# Boom_Control_Board.net
KiCad netlist of a schematic drawn in EAGLE
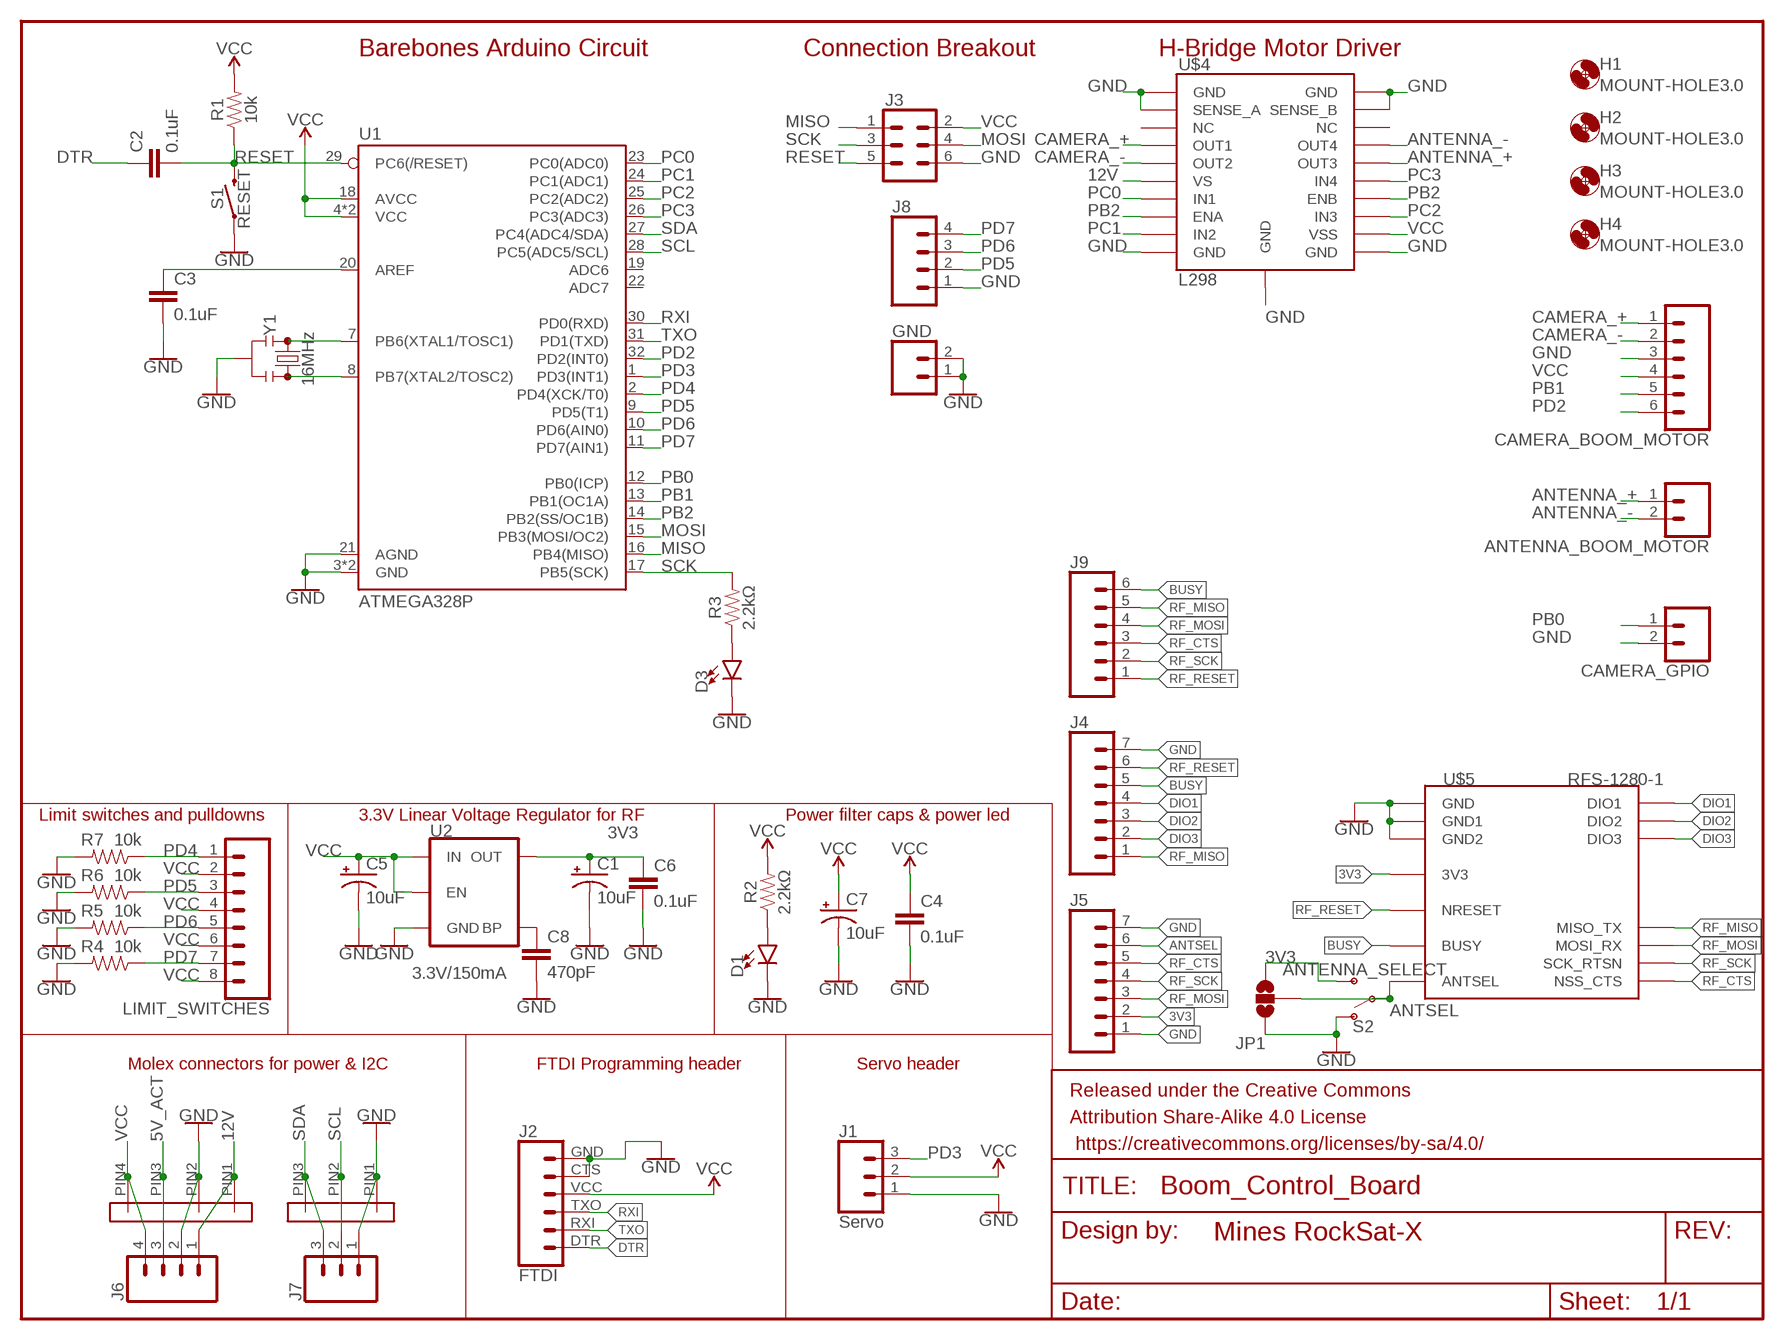
[diagram p0: schematic, sheet 1]

(export (version "E")
  (design (tool "Eeschema 10.0.6"))
  (components
    (comp (ref "ANTENNA_BOOM_MOTOR")
      (value "CONN_02LOCK_LONGPADS")
      (footprint "eagle-import:1X02_LOCK_LONGPADS")
      (libsource (lib "eagle-import") (part "CONN_02LOCK_LONGPADS"))
    )
    (comp (ref "C1")
      (value "10uF")
      (footprint "eagle-import:EIA3216")
      (libsource (lib "eagle-import") (part "10UF-POLAR-EIA3216-16V-10%(TANT)"))
    )
    (comp (ref "C2")
      (value "0.1uF")
      (footprint "eagle-import:0805")
      (libsource (lib "eagle-import") (part "2.2UF-0805-25V-(+80/-20%)"))
    )
    (comp (ref "C3")
      (value "0.1uF")
      (footprint "eagle-import:0805")
      (libsource (lib "eagle-import") (part "2.2UF-0805-25V-(+80/-20%)"))
    )
    (comp (ref "C4")
      (value "0.1uF")
      (footprint "eagle-import:0805")
      (libsource (lib "eagle-import") (part "2.2UF-0805-25V-(+80/-20%)"))
    )
    (comp (ref "C5")
      (value "10uF")
      (footprint "eagle-import:EIA3216")
      (libsource (lib "eagle-import") (part "10UF-POLAR-EIA3216-16V-10%(TANT)"))
    )
    (comp (ref "C6")
      (value "0.1uF")
      (footprint "eagle-import:0805")
      (libsource (lib "eagle-import") (part "2.2UF-0805-25V-(+80/-20%)"))
    )
    (comp (ref "C7")
      (value "10uF")
      (footprint "eagle-import:EIA3216")
      (libsource (lib "eagle-import") (part "10UF-POLAR-EIA3216-16V-10%(TANT)"))
    )
    (comp (ref "C8")
      (value "470pF")
      (footprint "eagle-import:0805")
      (libsource (lib "eagle-import") (part "CAP-0805"))
    )
    (comp (ref "CAMERA_BOOM_MOTOR")
      (value "CONN_06LOCK_LONGPADS")
      (footprint "eagle-import:1X06_LOCK_LONGPADS")
      (libsource (lib "eagle-import") (part "CONN_06LOCK_LONGPADS"))
    )
    (comp (ref "CAMERA_GPIO")
      (value "CONN_02LOCK_LONGPADS")
      (footprint "eagle-import:1X02_LOCK_LONGPADS")
      (libsource (lib "eagle-import") (part "CONN_02LOCK_LONGPADS"))
    )
    (comp (ref "D1")
      (value "LED-GREEN1206")
      (footprint "eagle-import:LED-1206")
      (libsource (lib "eagle-import") (part "LED-GREEN1206"))
    )
    (comp (ref "D3")
      (value "LED-GREEN1206")
      (footprint "eagle-import:LED-1206")
      (libsource (lib "eagle-import") (part "LED-GREEN1206"))
    )
    (comp (ref "FRAME1")
      (value "FRAME-LETTERNO_PACKAGE")
      (footprint "eagle-import:DUMMY")
      (fields
        (field (name "DESIGNER") "Mines RockSat-X")
        (field (name "VERSION") "1")
        (field (name "DESIGNER_1") "Mines RockSat-X")
      )
      (libsource (lib "eagle-import") (part "FRAME-LETTERNO_PACKAGE"))
    )
    (comp (ref "GND")
      (value "CONN_02LOCK_LONGPADS")
      (footprint "eagle-import:1X02_LOCK_LONGPADS")
      (libsource (lib "eagle-import") (part "CONN_02LOCK_LONGPADS"))
    )
    (comp (ref "H1")
      (value "MOUNT-HOLE3.0")
      (footprint "eagle-import:3,0")
      (libsource (lib "eagle-import") (part "MOUNT-HOLE3.0"))
    )
    (comp (ref "H2")
      (value "MOUNT-HOLE3.0")
      (footprint "eagle-import:3,0")
      (libsource (lib "eagle-import") (part "MOUNT-HOLE3.0"))
    )
    (comp (ref "H3")
      (value "MOUNT-HOLE3.0")
      (footprint "eagle-import:3,0")
      (libsource (lib "eagle-import") (part "MOUNT-HOLE3.0"))
    )
    (comp (ref "H4")
      (value "MOUNT-HOLE3.0")
      (footprint "eagle-import:3,0")
      (libsource (lib "eagle-import") (part "MOUNT-HOLE3.0"))
    )
    (comp (ref "J1")
      (value "Servo")
      (footprint "eagle-import:1X03")
      (libsource (lib "eagle-import") (part "CONN_03"))
    )
    (comp (ref "J2")
      (value "FTDI")
      (footprint "eagle-import:FTDI_BASIC")
      (libsource (lib "eagle-import") (part "6_PIN_SERIAL_CABLEPTH"))
    )
    (comp (ref "J3")
      (value "CONN_03X22X3_SILK_MALE_PTH")
      (footprint "eagle-import:2X3")
      (libsource (lib "eagle-import") (part "CONN_03X22X3_SILK_MALE_PTH"))
    )
    (comp (ref "J4")
      (value "CONN_07LOCK")
      (footprint "eagle-import:1X07_LOCK")
      (libsource (lib "eagle-import") (part "CONN_07LOCK"))
    )
    (comp (ref "J5")
      (value "CONN_07LOCK")
      (footprint "eagle-import:1X07_LOCK")
      (libsource (lib "eagle-import") (part "CONN_07LOCK"))
    )
    (comp (ref "J6")
      (value "CONN_04LOCK")
      (footprint "eagle-import:1X04_LOCK")
      (libsource (lib "eagle-import") (part "CONN_04LOCK"))
    )
    (comp (ref "J7")
      (value "CONN_03")
      (footprint "eagle-import:1X03")
      (libsource (lib "eagle-import") (part "CONN_03"))
    )
    (comp (ref "J8")
      (value "CONN_04LOCK")
      (footprint "eagle-import:1X04_LOCK")
      (libsource (lib "eagle-import") (part "CONN_04LOCK"))
    )
    (comp (ref "J9")
      (value "CONN_06LOCK")
      (footprint "eagle-import:1X06_LOCK")
      (libsource (lib "eagle-import") (part "CONN_06LOCK"))
    )
    (comp (ref "JP1")
      (value "JUMPER-SMT_3_NO_NO_SILK")
      (footprint "eagle-import:SMT-JUMPER_3_0-NO_TRACE_NO-SILK")
      (libsource (lib "eagle-import") (part "JUMPER-SMT_3_NO_NO_SILK"))
    )
    (comp (ref "LIMIT_SWITCHES")
      (value "CONN_08LOCK_LONGPADS")
      (footprint "eagle-import:1X08_LOCK_LONGPADS")
      (libsource (lib "eagle-import") (part "CONN_08LOCK_LONGPADS"))
    )
    (comp (ref "R1")
      (value "10k")
      (footprint "eagle-import:0805")
      (libsource (lib "eagle-import") (part "RESISTOR0805"))
    )
    (comp (ref "R2")
      (value "2.2kΩ")
      (footprint "eagle-import:0805")
      (libsource (lib "eagle-import") (part "RESISTOR0805"))
    )
    (comp (ref "R3")
      (value "2.2kΩ")
      (footprint "eagle-import:0805")
      (libsource (lib "eagle-import") (part "RESISTOR0805"))
    )
    (comp (ref "R4")
      (value "10k")
      (footprint "eagle-import:0805")
      (libsource (lib "eagle-import") (part "RESISTOR0805"))
    )
    (comp (ref "R5")
      (value "10k")
      (footprint "eagle-import:0805")
      (libsource (lib "eagle-import") (part "RESISTOR0805"))
    )
    (comp (ref "R6")
      (value "10k")
      (footprint "eagle-import:0805")
      (libsource (lib "eagle-import") (part "RESISTOR0805"))
    )
    (comp (ref "R7")
      (value "10k")
      (footprint "eagle-import:0805")
      (libsource (lib "eagle-import") (part "RESISTOR0805"))
    )
    (comp (ref "S1")
      (value "RESET")
      (footprint "eagle-import:TACTILE_SWITCH_SMD_5.2MM")
      (libsource (lib "eagle-import") (part "MOMENTARY-SWITCH-SPST-SMD-5.2-REDUNDANT"))
    )
    (comp (ref "S2")
      (value "ANTENNA_SELECT")
      (footprint "eagle-import:SWITCH_SPDT_PTH_11.6X4.0MM")
      (libsource (lib "eagle-import") (part "SWITCH-SPDT-PTH-11.6X4.0MM"))
    )
    (comp (ref "U$1")
      (value "MOLEX_4PIN")
      (footprint "eagle-import:MOLEX_4PIN")
      (libsource (lib "eagle-import") (part "MOLEX_4PIN"))
    )
    (comp (ref "U$2")
      (value "MOLEX_3PIN")
      (footprint "eagle-import:MOLEX_3PIN")
      (libsource (lib "eagle-import") (part "MOLEX_3PIN"))
    )
    (comp (ref "U$4")
      (value "L298")
      (footprint "eagle-import:POWERSO20_L298_PAD")
      (libsource (lib "eagle-import") (part "L298_SMD_W_PAD"))
    )
    (comp (ref "U$5")
      (value "RFS-1280-1")
      (footprint "eagle-import:RFS-1280-1")
      (libsource (lib "eagle-import") (part "RFS-1280-1"))
    )
    (comp (ref "U1")
      (value "ATMEGA328P")
      (footprint "eagle-import:TQFP32-08")
      (libsource (lib "eagle-import") (part "ATMEGA328P_TQFP"))
    )
    (comp (ref "U2")
      (value "3.3V/150mA")
      (footprint "eagle-import:SOT23-5")
      (libsource (lib "eagle-import") (part "V_REG_MIC52053.3V"))
    )
    (comp (ref "Y1")
      (value "16MHz")
      (footprint "eagle-import:RESONATOR-SMD-3.2X1.3")
      (libsource (lib "eagle-import") (part "RESONATOR-16MHZSMD_3.2X1.3"))
    )
  )
  (nets
    (net (code "1") (name "/5V_ACT") (class "Default")
      (node (ref "J6") (pin "3") (pinfunction "3_3") (pintype "passive"))
      (node (ref "U$1") (pin "PIN3") (pinfunction "PIN3_PIN3") (pintype "bidirectional"))
    )
    (net (code "2") (name "/12V") (class "Default")
      (node (ref "J6") (pin "1") (pinfunction "1_1") (pintype "passive"))
      (node (ref "U$1") (pin "PIN1") (pinfunction "PIN1_PIN1") (pintype "bidirectional"))
      (node (ref "U$4") (pin "6") (pinfunction "VS_6") (pintype "bidirectional"))
    )
    (net (code "3") (name "/ANTENNA_+") (class "Default")
      (node (ref "ANTENNA_BOOM_MOTOR") (pin "1") (pinfunction "1_1") (pintype "passive"))
      (node (ref "U$4") (pin "16") (pinfunction "OUT3_16") (pintype "bidirectional"))
    )
    (net (code "4") (name "/ANTENNA_-") (class "Default")
      (node (ref "ANTENNA_BOOM_MOTOR") (pin "2") (pinfunction "2_2") (pintype "passive"))
      (node (ref "U$4") (pin "17") (pinfunction "OUT4_17") (pintype "bidirectional"))
    )
    (net (code "5") (name "/CAMERA_+") (class "Default")
      (node (ref "CAMERA_BOOM_MOTOR") (pin "1") (pinfunction "1_1") (pintype "passive"))
      (node (ref "U$4") (pin "4") (pinfunction "OUT1_4") (pintype "bidirectional"))
    )
    (net (code "6") (name "/CAMERA_-") (class "Default")
      (node (ref "CAMERA_BOOM_MOTOR") (pin "2") (pinfunction "2_2") (pintype "passive"))
      (node (ref "U$4") (pin "5") (pinfunction "OUT2_5") (pintype "bidirectional"))
    )
    (net (code "7") (name "/MISO") (class "Default")
      (node (ref "J3") (pin "1") (pinfunction "1_1") (pintype "bidirectional"))
      (node (ref "U1") (pin "16") (pinfunction "PB4(MISO)_16") (pintype "bidirectional"))
    )
    (net (code "8") (name "/MOSI") (class "Default")
      (node (ref "J3") (pin "4") (pinfunction "4_4") (pintype "bidirectional"))
      (node (ref "U1") (pin "15") (pinfunction "PB3(MOSI/OC2)_15") (pintype "bidirectional"))
    )
    (net (code "9") (name "/PB0") (class "Default")
      (node (ref "CAMERA_GPIO") (pin "1") (pinfunction "1_1") (pintype "passive"))
      (node (ref "U1") (pin "12") (pinfunction "PB0(ICP)_12") (pintype "bidirectional"))
    )
    (net (code "10") (name "/PB1") (class "Default")
      (node (ref "CAMERA_BOOM_MOTOR") (pin "5") (pinfunction "5_5") (pintype "passive"))
      (node (ref "U1") (pin "13") (pinfunction "PB1(OC1A)_13") (pintype "bidirectional"))
    )
    (net (code "11") (name "/PB2") (class "Default")
      (node (ref "U$4") (pin "14") (pinfunction "ENB_14") (pintype "bidirectional"))
      (node (ref "U$4") (pin "8") (pinfunction "ENA_8") (pintype "bidirectional"))
      (node (ref "U1") (pin "14") (pinfunction "PB2(SS/OC1B)_14") (pintype "bidirectional"))
    )
    (net (code "12") (name "/PC0") (class "Default")
      (node (ref "U$4") (pin "7") (pinfunction "IN1_7") (pintype "bidirectional"))
      (node (ref "U1") (pin "23") (pinfunction "PC0(ADC0)_23") (pintype "bidirectional"))
    )
    (net (code "13") (name "/PC1") (class "Default")
      (node (ref "U$4") (pin "9") (pinfunction "IN2_9") (pintype "bidirectional"))
      (node (ref "U1") (pin "24") (pinfunction "PC1(ADC1)_24") (pintype "bidirectional"))
    )
    (net (code "14") (name "/PC2") (class "Default")
      (node (ref "U$4") (pin "13") (pinfunction "IN3_13") (pintype "bidirectional"))
      (node (ref "U1") (pin "25") (pinfunction "PC2(ADC2)_25") (pintype "bidirectional"))
    )
    (net (code "15") (name "/PC3") (class "Default")
      (node (ref "U$4") (pin "15") (pinfunction "IN4_15") (pintype "bidirectional"))
      (node (ref "U1") (pin "26") (pinfunction "PC3(ADC3)_26") (pintype "bidirectional"))
    )
    (net (code "16") (name "/PD2") (class "Default")
      (node (ref "CAMERA_BOOM_MOTOR") (pin "6") (pinfunction "6_6") (pintype "passive"))
      (node (ref "U1") (pin "32") (pinfunction "PD2(INT0)_32") (pintype "bidirectional"))
    )
    (net (code "17") (name "/PD3") (class "Default")
      (node (ref "J1") (pin "3") (pinfunction "3_3") (pintype "passive"))
      (node (ref "U1") (pin "1") (pinfunction "PD3(INT1)_1") (pintype "bidirectional"))
    )
    (net (code "18") (name "/PD4") (class "Default")
      (node (ref "LIMIT_SWITCHES") (pin "1") (pinfunction "1_1") (pintype "passive"))
      (node (ref "R7") (pin "1") (pinfunction "1_1") (pintype "passive"))
      (node (ref "U1") (pin "2") (pinfunction "PD4(XCK/T0)_2") (pintype "bidirectional"))
    )
    (net (code "19") (name "/PD5") (class "Default")
      (node (ref "J8") (pin "2") (pinfunction "2_2") (pintype "passive"))
      (node (ref "LIMIT_SWITCHES") (pin "3") (pinfunction "3_3") (pintype "passive"))
      (node (ref "R6") (pin "1") (pinfunction "1_1") (pintype "passive"))
      (node (ref "U1") (pin "9") (pinfunction "PD5(T1)_9") (pintype "bidirectional"))
    )
    (net (code "20") (name "/PD6") (class "Default")
      (node (ref "J8") (pin "3") (pinfunction "3_3") (pintype "passive"))
      (node (ref "LIMIT_SWITCHES") (pin "5") (pinfunction "5_5") (pintype "passive"))
      (node (ref "R5") (pin "1") (pinfunction "1_1") (pintype "passive"))
      (node (ref "U1") (pin "10") (pinfunction "PD6(AIN0)_10") (pintype "bidirectional"))
    )
    (net (code "21") (name "/PD7") (class "Default")
      (node (ref "J8") (pin "4") (pinfunction "4_4") (pintype "passive"))
      (node (ref "LIMIT_SWITCHES") (pin "7") (pinfunction "7_7") (pintype "passive"))
      (node (ref "R4") (pin "1") (pinfunction "1_1") (pintype "passive"))
      (node (ref "U1") (pin "11") (pinfunction "PD7(AIN1)_11") (pintype "bidirectional"))
    )
    (net (code "22") (name "/RESET") (class "Default")
      (node (ref "C2") (pin "2") (pinfunction "2_2") (pintype "passive"))
      (node (ref "J3") (pin "5") (pinfunction "5_5") (pintype "bidirectional"))
      (node (ref "R1") (pin "1") (pinfunction "1_1") (pintype "passive"))
      (node (ref "S1") (pin "3") (pinfunction "2_3") (pintype "passive"))
      (node (ref "S1") (pin "4") (pinfunction "2_4") (pintype "passive"))
      (node (ref "U1") (pin "29") (pinfunction "PC6(/RESET)_29") (pintype "bidirectional"))
    )
    (net (code "23") (name "/SCK") (class "Default")
      (node (ref "J3") (pin "3") (pinfunction "3_3") (pintype "bidirectional"))
      (node (ref "R3") (pin "2") (pinfunction "2_2") (pintype "passive"))
      (node (ref "U1") (pin "17") (pinfunction "PB5(SCK)_17") (pintype "bidirectional"))
    )
    (net (code "24") (name "/SCL") (class "Default")
      (node (ref "J7") (pin "2") (pinfunction "2_2") (pintype "passive"))
      (node (ref "U$2") (pin "PIN2") (pinfunction "PIN2_PIN2") (pintype "bidirectional"))
      (node (ref "U1") (pin "28") (pinfunction "PC5(ADC5/SCL)_28") (pintype "bidirectional"))
    )
    (net (code "25") (name "/SDA") (class "Default")
      (node (ref "J7") (pin "3") (pinfunction "3_3") (pintype "passive"))
      (node (ref "U$2") (pin "PIN3") (pinfunction "PIN3_PIN3") (pintype "bidirectional"))
      (node (ref "U1") (pin "27") (pinfunction "PC4(ADC4/SDA)_27") (pintype "bidirectional"))
    )
    (net (code "26") (name "3V3") (class "Default")
      (node (ref "C1") (pin "+") (pinfunction "+_+") (pintype "passive"))
      (node (ref "C6") (pin "1") (pinfunction "1_1") (pintype "passive"))
      (node (ref "J5") (pin "2") (pinfunction "2_2") (pintype "passive"))
      (node (ref "JP1") (pin "3") (pinfunction "3_3") (pintype "passive"))
      (node (ref "S2") (pin "3") (pinfunction "S_3") (pintype "passive"))
      (node (ref "U$5") (pin "P$23") (pinfunction "3V3_P$23") (pintype "bidirectional"))
      (node (ref "U$5") (pin "P$9") (pinfunction "3V3_P$9") (pintype "bidirectional"))
      (node (ref "U2") (pin "5") (pinfunction "OUT_5") (pintype "passive"))
    )
    (net (code "27") (name "ANTSEL") (class "Default")
      (node (ref "J5") (pin "6") (pinfunction "6_6") (pintype "passive"))
      (node (ref "JP1") (pin "2") (pinfunction "2_2") (pintype "passive"))
      (node (ref "S2") (pin "2") (pinfunction "P_2") (pintype "passive"))
      (node (ref "U$5") (pin "P$13") (pinfunction "ANTSEL_P$13") (pintype "bidirectional"))
      (node (ref "U$5") (pin "P$27") (pinfunction "ANTSEL_P$27") (pintype "bidirectional"))
    )
    (net (code "28") (name "BUSY") (class "Default")
      (node (ref "J4") (pin "5") (pinfunction "5_5") (pintype "passive"))
      (node (ref "J9") (pin "6") (pinfunction "6_6") (pintype "passive"))
      (node (ref "U$5") (pin "P$17") (pinfunction "BUSY_P$17") (pintype "bidirectional"))
      (node (ref "U$5") (pin "P$3") (pinfunction "BUSY_P$3") (pintype "bidirectional"))
    )
    (net (code "29") (name "DIO1") (class "Default")
      (node (ref "J4") (pin "4") (pinfunction "4_4") (pintype "passive"))
      (node (ref "U$5") (pin "P$18") (pinfunction "DIO1_P$18") (pintype "bidirectional"))
      (node (ref "U$5") (pin "P$4") (pinfunction "DIO1_P$4") (pintype "bidirectional"))
    )
    (net (code "30") (name "DIO2") (class "Default")
      (node (ref "J4") (pin "3") (pinfunction "3_3") (pintype "passive"))
      (node (ref "U$5") (pin "P$19") (pinfunction "DIO2_P$19") (pintype "bidirectional"))
      (node (ref "U$5") (pin "P$5") (pinfunction "DIO2_P$5") (pintype "bidirectional"))
    )
    (net (code "31") (name "DIO3") (class "Default")
      (node (ref "J4") (pin "2") (pinfunction "2_2") (pintype "passive"))
      (node (ref "U$5") (pin "P$20") (pinfunction "DIO3_P$20") (pintype "bidirectional"))
      (node (ref "U$5") (pin "P$6") (pinfunction "DIO3_P$6") (pintype "bidirectional"))
    )
    (net (code "32") (name "DTR") (class "Default")
      (node (ref "C2") (pin "1") (pinfunction "1_1") (pintype "passive"))
      (node (ref "J2") (pin "DTR") (pinfunction "1_DTR") (pintype "passive"))
    )
    (net (code "33") (name "GND") (class "Default")
      (node (ref "C1") (pin "-") (pinfunction "-_-") (pintype "passive"))
      (node (ref "C3") (pin "2") (pinfunction "2_2") (pintype "passive"))
      (node (ref "C4") (pin "2") (pinfunction "2_2") (pintype "passive"))
      (node (ref "C5") (pin "-") (pinfunction "-_-") (pintype "passive"))
      (node (ref "C6") (pin "2") (pinfunction "2_2") (pintype "passive"))
      (node (ref "C7") (pin "-") (pinfunction "-_-") (pintype "passive"))
      (node (ref "C8") (pin "2") (pinfunction "2_2") (pintype "passive"))
      (node (ref "CAMERA_BOOM_MOTOR") (pin "3") (pinfunction "3_3") (pintype "passive"))
      (node (ref "CAMERA_GPIO") (pin "2") (pinfunction "2_2") (pintype "passive"))
      (node (ref "D1") (pin "C") (pinfunction "C_C") (pintype "passive"))
      (node (ref "D3") (pin "C") (pinfunction "C_C") (pintype "passive"))
      (node (ref "GND") (pin "1") (pinfunction "1_1") (pintype "passive"))
      (node (ref "GND") (pin "2") (pinfunction "2_2") (pintype "passive"))
      (node (ref "J1") (pin "1") (pinfunction "1_1") (pintype "passive"))
      (node (ref "J2") (pin "CTS") (pinfunction "5_CTS") (pintype "passive"))
      (node (ref "J2") (pin "GND") (pinfunction "6_GND") (pintype "passive"))
      (node (ref "J3") (pin "6") (pinfunction "6_6") (pintype "bidirectional"))
      (node (ref "J4") (pin "7") (pinfunction "7_7") (pintype "passive"))
      (node (ref "J5") (pin "1") (pinfunction "1_1") (pintype "passive"))
      (node (ref "J5") (pin "7") (pinfunction "7_7") (pintype "passive"))
      (node (ref "J6") (pin "2") (pinfunction "2_2") (pintype "passive"))
      (node (ref "J7") (pin "1") (pinfunction "1_1") (pintype "passive"))
      (node (ref "J8") (pin "1") (pinfunction "1_1") (pintype "passive"))
      (node (ref "JP1") (pin "1") (pinfunction "1_1") (pintype "passive"))
      (node (ref "R4") (pin "2") (pinfunction "2_2") (pintype "passive"))
      (node (ref "R5") (pin "2") (pinfunction "2_2") (pintype "passive"))
      (node (ref "R6") (pin "2") (pinfunction "2_2") (pintype "passive"))
      (node (ref "R7") (pin "2") (pinfunction "2_2") (pintype "passive"))
      (node (ref "S1") (pin "1") (pinfunction "1_1") (pintype "passive"))
      (node (ref "S1") (pin "2") (pinfunction "1_2") (pintype "passive"))
      (node (ref "S2") (pin "1") (pinfunction "O_1") (pintype "passive"))
      (node (ref "U$1") (pin "PIN2") (pinfunction "PIN2_PIN2") (pintype "bidirectional"))
      (node (ref "U$2") (pin "PIN1") (pinfunction "PIN1_PIN1") (pintype "bidirectional"))
      (node (ref "U$4") (pin "1") (pinfunction "GND_1") (pintype "bidirectional"))
      (node (ref "U$4") (pin "10") (pinfunction "GND_10") (pintype "bidirectional"))
      (node (ref "U$4") (pin "11") (pinfunction "GND_11") (pintype "bidirectional"))
      (node (ref "U$4") (pin "19") (pinfunction "SENSE_B_19") (pintype "bidirectional"))
      (node (ref "U$4") (pin "2") (pinfunction "SENSE_A_2") (pintype "bidirectional"))
      (node (ref "U$4") (pin "20") (pinfunction "GND_20") (pintype "bidirectional"))
      (node (ref "U$4") (pin "PAD") (pinfunction "GND_PAD") (pintype "bidirectional"))
      (node (ref "U$5") (pin "P$1") (pinfunction "GND_P$1") (pintype "bidirectional"))
      (node (ref "U$5") (pin "P$14") (pinfunction "GND2_P$14") (pintype "bidirectional"))
      (node (ref "U$5") (pin "P$15") (pinfunction "GND_P$15") (pintype "bidirectional"))
      (node (ref "U$5") (pin "P$22") (pinfunction "GND1_P$22") (pintype "bidirectional"))
      (node (ref "U$5") (pin "P$28") (pinfunction "GND2_P$28") (pintype "bidirectional"))
      (node (ref "U$5") (pin "P$8") (pinfunction "GND1_P$8") (pintype "bidirectional"))
      (node (ref "U1") (pin "21") (pinfunction "AGND_21") (pintype "bidirectional"))
      (node (ref "U1") (pin "3") (pinfunction "GND_3") (pintype "bidirectional"))
      (node (ref "U1") (pin "5") (pinfunction "GND_5") (pintype "bidirectional"))
      (node (ref "U2") (pin "2") (pinfunction "GND_2") (pintype "input"))
      (node (ref "Y1") (pin "2") (pinfunction "2_2") (pintype "passive"))
    )
    (net (code "34") (name "Net-(D1-PadA)") (class "Default")
      (node (ref "D1") (pin "A") (pinfunction "A_A") (pintype "passive"))
      (node (ref "R2") (pin "1") (pinfunction "1_1") (pintype "passive"))
    )
    (net (code "35") (name "Net-(D3-PadA)") (class "Default")
      (node (ref "D3") (pin "A") (pinfunction "A_A") (pintype "passive"))
      (node (ref "R3") (pin "1") (pinfunction "1_1") (pintype "passive"))
    )
    (net (code "36") (name "Net-(U1-AREF)") (class "Default")
      (node (ref "C3") (pin "1") (pinfunction "1_1") (pintype "passive"))
      (node (ref "U1") (pin "20") (pinfunction "AREF_20") (pintype "bidirectional"))
    )
    (net (code "37") (name "Net-(U1-PB6(XTAL1{slash}TOSC1))") (class "Default")
      (node (ref "U1") (pin "7") (pinfunction "PB6(XTAL1/TOSC1)_7") (pintype "bidirectional"))
      (node (ref "Y1") (pin "1") (pinfunction "1_1") (pintype "passive"))
    )
    (net (code "38") (name "Net-(U1-PB7(XTAL2{slash}TOSC2))") (class "Default")
      (node (ref "U1") (pin "8") (pinfunction "PB7(XTAL2/TOSC2)_8") (pintype "bidirectional"))
      (node (ref "Y1") (pin "3") (pinfunction "3_3") (pintype "passive"))
    )
    (net (code "39") (name "Net-(U2-BP)") (class "Default")
      (node (ref "C8") (pin "1") (pinfunction "1_1") (pintype "passive"))
      (node (ref "U2") (pin "4") (pinfunction "BP_4") (pintype "input"))
    )
    (net (code "40") (name "RF_CTS") (class "Default")
      (node (ref "J5") (pin "5") (pinfunction "5_5") (pintype "passive"))
      (node (ref "J9") (pin "3") (pinfunction "3_3") (pintype "passive"))
      (node (ref "U$5") (pin "P$12") (pinfunction "NSS_CTS_P$12") (pintype "bidirectional"))
      (node (ref "U$5") (pin "P$26") (pinfunction "NSS_CTS_P$26") (pintype "bidirectional"))
    )
    (net (code "41") (name "RF_MISO") (class "Default")
      (node (ref "J4") (pin "1") (pinfunction "1_1") (pintype "passive"))
      (node (ref "J9") (pin "5") (pinfunction "5_5") (pintype "passive"))
      (node (ref "U$5") (pin "P$21") (pinfunction "MISO_TX_P$21") (pintype "bidirectional"))
      (node (ref "U$5") (pin "P$7") (pinfunction "MISO_TX_P$7") (pintype "bidirectional"))
    )
    (net (code "42") (name "RF_MOSI") (class "Default")
      (node (ref "J5") (pin "3") (pinfunction "3_3") (pintype "passive"))
      (node (ref "J9") (pin "4") (pinfunction "4_4") (pintype "passive"))
      (node (ref "U$5") (pin "P$10") (pinfunction "MOSI_RX_P$10") (pintype "bidirectional"))
      (node (ref "U$5") (pin "P$24") (pinfunction "MOSI_RX_P$24") (pintype "bidirectional"))
    )
    (net (code "43") (name "RF_RESET") (class "Default")
      (node (ref "J4") (pin "6") (pinfunction "6_6") (pintype "passive"))
      (node (ref "J9") (pin "1") (pinfunction "1_1") (pintype "passive"))
      (node (ref "U$5") (pin "P$16") (pinfunction "NRESET_P$16") (pintype "bidirectional"))
      (node (ref "U$5") (pin "P$2") (pinfunction "NRESET_P$2") (pintype "bidirectional"))
    )
    (net (code "44") (name "RF_SCK") (class "Default")
      (node (ref "J5") (pin "4") (pinfunction "4_4") (pintype "passive"))
      (node (ref "J9") (pin "2") (pinfunction "2_2") (pintype "passive"))
      (node (ref "U$5") (pin "P$11") (pinfunction "SCK_RTSN_P$11") (pintype "bidirectional"))
      (node (ref "U$5") (pin "P$25") (pinfunction "SCK_RTSN_P$25") (pintype "bidirectional"))
    )
    (net (code "45") (name "RXI") (class "Default")
      (node (ref "J2") (pin "TXO") (pinfunction "3_TXO") (pintype "passive"))
      (node (ref "U1") (pin "30") (pinfunction "PD0(RXD)_30") (pintype "bidirectional"))
    )
    (net (code "46") (name "TXO") (class "Default")
      (node (ref "J2") (pin "RXI") (pinfunction "2_RXI") (pintype "passive"))
      (node (ref "U1") (pin "31") (pinfunction "PD1(TXD)_31") (pintype "bidirectional"))
    )
    (net (code "47") (name "VCC") (class "Default")
      (node (ref "C4") (pin "1") (pinfunction "1_1") (pintype "passive"))
      (node (ref "C5") (pin "+") (pinfunction "+_+") (pintype "passive"))
      (node (ref "C7") (pin "+") (pinfunction "+_+") (pintype "passive"))
      (node (ref "CAMERA_BOOM_MOTOR") (pin "4") (pinfunction "4_4") (pintype "passive"))
      (node (ref "J1") (pin "2") (pinfunction "2_2") (pintype "passive"))
      (node (ref "J2") (pin "VCC") (pinfunction "4_VCC") (pintype "passive"))
      (node (ref "J3") (pin "2") (pinfunction "2_2") (pintype "bidirectional"))
      (node (ref "J6") (pin "4") (pinfunction "4_4") (pintype "passive"))
      (node (ref "LIMIT_SWITCHES") (pin "2") (pinfunction "2_2") (pintype "passive"))
      (node (ref "LIMIT_SWITCHES") (pin "4") (pinfunction "4_4") (pintype "passive"))
      (node (ref "LIMIT_SWITCHES") (pin "6") (pinfunction "6_6") (pintype "passive"))
      (node (ref "LIMIT_SWITCHES") (pin "8") (pinfunction "8_8") (pintype "passive"))
      (node (ref "R1") (pin "2") (pinfunction "2_2") (pintype "passive"))
      (node (ref "R2") (pin "2") (pinfunction "2_2") (pintype "passive"))
      (node (ref "U$1") (pin "PIN4") (pinfunction "PIN4_PIN4") (pintype "bidirectional"))
      (node (ref "U$4") (pin "12") (pinfunction "VSS_12") (pintype "bidirectional"))
      (node (ref "U1") (pin "18") (pinfunction "AVCC_18") (pintype "bidirectional"))
      (node (ref "U1") (pin "4") (pinfunction "VCC_4") (pintype "bidirectional"))
      (node (ref "U1") (pin "6") (pinfunction "VCC_6") (pintype "bidirectional"))
      (node (ref "U2") (pin "1") (pinfunction "IN_1") (pintype "input"))
      (node (ref "U2") (pin "3") (pinfunction "EN_3") (pintype "input"))
    )
    (net (code "48") (name "unconnected-(U$4-NC-Pad3)") (class "Default")
      (node (ref "U$4") (pin "3") (pinfunction "NC_3") (pintype "bidirectional"))
    )
    (net (code "49") (name "unconnected-(U$4-NC-Pad18)") (class "Default")
      (node (ref "U$4") (pin "18") (pinfunction "NC_18") (pintype "bidirectional"))
    )
    (net (code "50") (name "unconnected-(U1-ADC6-Pad19)") (class "Default")
      (node (ref "U1") (pin "19") (pinfunction "ADC6_19") (pintype "bidirectional"))
    )
    (net (code "51") (name "unconnected-(U1-ADC7-Pad22)") (class "Default")
      (node (ref "U1") (pin "22") (pinfunction "ADC7_22") (pintype "bidirectional"))
    )
  )
)
